# 20_-CONNECT_CONNECTORS.net
KiCad netlist of a schematic drawn in Altium Designer
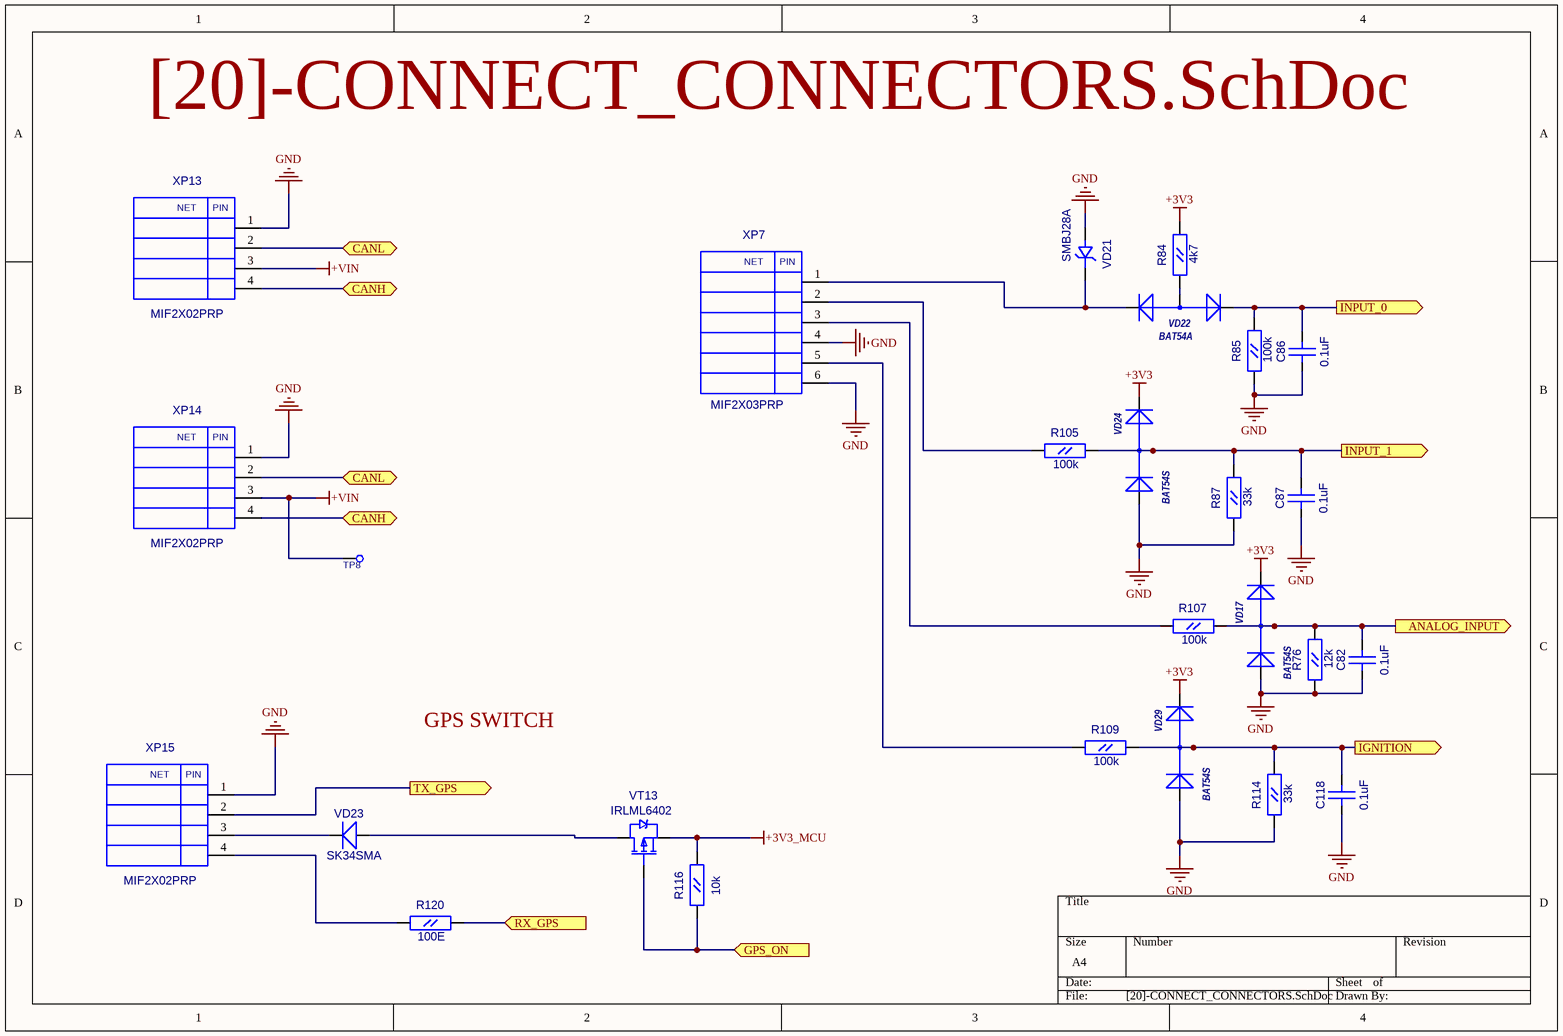
[diagram p0: [20]-CONNECT_CONNECTORS.SchDoc]

(export (version "E")
  (design (tool "Eeschema 10.0.6"))
  (components
    (comp (ref "C82")
      (value "0.1uF")
      (footprint "CC0603")
      (description "CC0603")
      (libsource (lib "gprs_modem_2") (part "CC0603"))
    )
    (comp (ref "C86")
      (value "0.1uF")
      (footprint "CC0603")
      (description "CC0603")
      (libsource (lib "fizik_lib") (part "CC0603"))
    )
    (comp (ref "C87")
      (value "0.1uF")
      (footprint "CC0603")
      (description "CC0603")
      (libsource (lib "gprs_modem_2") (part "CC0603"))
    )
    (comp (ref "C118")
      (value "0.1uF")
      (footprint "CC0603")
      (description "CC0603")
      (libsource (lib "gprs_modem_2") (part "CC0603"))
    )
    (comp (ref "R76")
      (value "12k")
      (footprint "RC0603")
      (description "RC0603")
      (libsource (lib "gprs_modem_2") (part "RC0603"))
    )
    (comp (ref "R84")
      (value "4k7")
      (footprint "RC0603")
      (description "RC0603")
      (libsource (lib "fizik_lib") (part "RC0603"))
    )
    (comp (ref "R85")
      (value "100k")
      (footprint "RC0603")
      (description "RC0603")
      (libsource (lib "fizik_lib") (part "RC0603"))
    )
    (comp (ref "R87")
      (value "33k")
      (footprint "RC0603")
      (description "RC0603")
      (libsource (lib "fizik_lib") (part "RC0603"))
    )
    (comp (ref "R105")
      (value "100k")
      (footprint "RC0603")
      (description "RC0603")
      (libsource (lib "gprs_modem_2") (part "RC0603"))
    )
    (comp (ref "R107")
      (value "100k")
      (footprint "RC0603")
      (description "RC0603")
      (libsource (lib "gprs_modem_2") (part "RC0603"))
    )
    (comp (ref "R109")
      (value "100k")
      (footprint "RC0603")
      (description "RC0603")
      (libsource (lib "gprs_modem_2") (part "RC0603"))
    )
    (comp (ref "R114")
      (value "33k")
      (footprint "RC0603")
      (description "RC0603")
      (libsource (lib "fizik_lib") (part "RC0603"))
    )
    (comp (ref "R116")
      (value "10k")
      (footprint "RC0603")
      (description "RC0603")
      (libsource (lib "gprs_modem_2") (part "RC0603"))
    )
    (comp (ref "R120")
      (value "100E")
      (footprint "RC0603")
      (description "RC0603")
      (libsource (lib "fizik_lib (1)") (part "RC0603"))
    )
    (comp (ref "TP8")
      (value "TESTPOINT1")
      (footprint "TESTPOINT1")
      (libsource (lib "fizik_lib (1)") (part "TESTPOINT1"))
    )
    (comp (ref "VD17")
      (value "BAT54S")
      (footprint "SOT-23(GSD)")
      (description "1.0 Ampere General Purpose Rectifier")
      (libsource (lib "gprs_modem_2") (part "BAT54S"))
    )
    (comp (ref "VD21")
      (value "SMBJ28A")
      (footprint "SMB")
      (description "SMBJ")
      (libsource (lib "fizik_lib") (part "SMBJ"))
    )
    (comp (ref "VD22")
      (value "BAT54A")
      (footprint "SOT-23(123)")
      (description "1.0 Ampere General Purpose Rectifier")
      (libsource (lib "fizik_lib") (part "BAT54A"))
    )
    (comp (ref "VD23")
      (value "SK34SMA")
      (footprint "SMA")
      (description "Schottky Rectifier")
      (libsource (lib "fizik_lib") (part "SK34SMA"))
    )
    (comp (ref "VD24")
      (value "BAT54S")
      (footprint "SOT-23(GSD)")
      (description "1.0 Ampere General Purpose Rectifier")
      (libsource (lib "fizik_lib") (part "BAT54S"))
    )
    (comp (ref "VD29")
      (value "BAT54S")
      (footprint "SOT-23(GSD)")
      (description "1.0 Ampere General Purpose Rectifier")
      (libsource (lib "fizik_lib") (part "BAT54S"))
    )
    (comp (ref "VT13")
      (value "IRLML6402")
      (footprint "SOT-23(123)")
      (description "HEXFET Power MOSFET")
      (libsource (lib "gprs_modem_2") (part "IRLML6402"))
    )
    (comp (ref "XP7")
      (value "MIF2X03PRP")
      (footprint "MIF2X03PRP")
      (libsource (lib "fizik_lib (1)") (part "MIF2X03PRP"))
    )
    (comp (ref "XP13")
      (value "MIF2X02PRP")
      (footprint "MIF2X02PRP")
      (libsource (lib "fizik_lib") (part "MIF2X02PRP"))
    )
    (comp (ref "XP14")
      (value "MIF2X02PRP")
      (footprint "MIF2X02PRP")
      (libsource (lib "fizik_lib") (part "MIF2X02PRP"))
    )
    (comp (ref "XP15")
      (value "MIF2X02PRP")
      (footprint "MIF2X02PRP")
      (libsource (lib "fizik_lib") (part "MIF2X02PRP"))
    )
  )
  (nets
    (net (code "1") (name "+3V3") (class "Default")
      (node (ref "R84") (pin "2") (pinfunction "B_2") (pintype "passive"))
      (node (ref "VD17") (pin "2") (pinfunction "K_2") (pintype "passive"))
      (node (ref "VD24") (pin "2") (pinfunction "K_2") (pintype "passive"))
      (node (ref "VD29") (pin "2") (pinfunction "K_2") (pintype "passive"))
    )
    (net (code "2") (name "+3V3_MCU") (class "Default")
      (node (ref "R116") (pin "2") (pinfunction "B_2") (pintype "passive"))
      (node (ref "VT13") (pin "2") (pinfunction "S_2") (pintype "passive"))
    )
    (net (code "3") (name "+VIN") (class "Default")
      (node (ref "TP8") (pin "1") (pintype "passive"))
      (node (ref "XP13") (pin "3") (pinfunction "3_3") (pintype "passive"))
      (node (ref "XP14") (pin "3") (pinfunction "3_3") (pintype "passive"))
    )
    (net (code "4") (name "/ANALOG_INPUT") (class "Default")
      (node (ref "C82") (pin "2") (pinfunction "B_2") (pintype "passive"))
      (node (ref "R107") (pin "2") (pinfunction "B_2") (pintype "passive"))
      (node (ref "R76") (pin "2") (pinfunction "B_2") (pintype "passive"))
      (node (ref "VD17") (pin "3") (pinfunction "AK_3") (pintype "passive"))
    )
    (net (code "5") (name "/CANH") (class "Default")
      (node (ref "XP13") (pin "4") (pinfunction "4_4") (pintype "passive"))
      (node (ref "XP14") (pin "4") (pinfunction "4_4") (pintype "passive"))
    )
    (net (code "6") (name "/CANL") (class "Default")
      (node (ref "XP13") (pin "2") (pinfunction "2_2") (pintype "passive"))
      (node (ref "XP14") (pin "2") (pinfunction "2_2") (pintype "passive"))
    )
    (net (code "7") (name "/GPS_ON") (class "Default")
      (node (ref "R116") (pin "1") (pinfunction "A_1") (pintype "passive"))
      (node (ref "VT13") (pin "1") (pinfunction "G_1") (pintype "passive"))
    )
    (net (code "8") (name "/IGNITION") (class "Default")
      (node (ref "C118") (pin "2") (pinfunction "B_2") (pintype "passive"))
      (node (ref "R109") (pin "2") (pinfunction "B_2") (pintype "passive"))
      (node (ref "R114") (pin "2") (pinfunction "B_2") (pintype "passive"))
      (node (ref "VD29") (pin "3") (pinfunction "AK_3") (pintype "passive"))
    )
    (net (code "9") (name "/INPUT_0") (class "Default")
      (node (ref "C86") (pin "2") (pinfunction "B_2") (pintype "passive"))
      (node (ref "R85") (pin "2") (pinfunction "B_2") (pintype "passive"))
      (node (ref "VD22") (pin "2") (pinfunction "K_2") (pintype "passive"))
    )
    (net (code "10") (name "/INPUT_1") (class "Default")
      (node (ref "C87") (pin "2") (pinfunction "B_2") (pintype "passive"))
      (node (ref "R105") (pin "2") (pinfunction "B_2") (pintype "passive"))
      (node (ref "R87") (pin "2") (pinfunction "B_2") (pintype "passive"))
      (node (ref "VD24") (pin "3") (pinfunction "AK_3") (pintype "passive"))
    )
    (net (code "11") (name "/RX_GPS") (class "Default")
      (node (ref "R120") (pin "2") (pinfunction "B_2") (pintype "passive"))
    )
    (net (code "12") (name "/TX_GPS") (class "Default")
      (node (ref "XP15") (pin "2") (pinfunction "2_2") (pintype "passive"))
    )
    (net (code "13") (name "GND") (class "Default")
      (node (ref "C118") (pin "1") (pinfunction "A_1") (pintype "passive"))
      (node (ref "C82") (pin "1") (pinfunction "A_1") (pintype "passive"))
      (node (ref "C86") (pin "1") (pinfunction "A_1") (pintype "passive"))
      (node (ref "C87") (pin "1") (pinfunction "A_1") (pintype "passive"))
      (node (ref "R114") (pin "1") (pinfunction "A_1") (pintype "passive"))
      (node (ref "R76") (pin "1") (pinfunction "A_1") (pintype "passive"))
      (node (ref "R85") (pin "1") (pinfunction "A_1") (pintype "passive"))
      (node (ref "R87") (pin "1") (pinfunction "A_1") (pintype "passive"))
      (node (ref "VD17") (pin "1") (pinfunction "A_1") (pintype "passive"))
      (node (ref "VD21") (pin "1") (pinfunction "A_1") (pintype "passive"))
      (node (ref "VD24") (pin "1") (pinfunction "A_1") (pintype "passive"))
      (node (ref "VD29") (pin "1") (pinfunction "A_1") (pintype "passive"))
      (node (ref "XP13") (pin "1") (pinfunction "1_1") (pintype "passive"))
      (node (ref "XP14") (pin "1") (pinfunction "1_1") (pintype "passive"))
      (node (ref "XP15") (pin "1") (pinfunction "1_1") (pintype "passive"))
      (node (ref "XP7") (pin "4") (pinfunction "4_4") (pintype "passive"))
      (node (ref "XP7") (pin "6") (pinfunction "6_6") (pintype "passive"))
    )
    (net (code "14") (name "Net-(R84-A)") (class "Default")
      (node (ref "R84") (pin "1") (pinfunction "A_1") (pintype "passive"))
      (node (ref "VD22") (pin "3") (pinfunction "A_3") (pintype "passive"))
    )
    (net (code "15") (name "Net-(R105-A)") (class "Default")
      (node (ref "R105") (pin "1") (pinfunction "A_1") (pintype "passive"))
      (node (ref "XP7") (pin "2") (pinfunction "2_2") (pintype "passive"))
    )
    (net (code "16") (name "Net-(R107-A)") (class "Default")
      (node (ref "R107") (pin "1") (pinfunction "A_1") (pintype "passive"))
      (node (ref "XP7") (pin "3") (pinfunction "3_3") (pintype "passive"))
    )
    (net (code "17") (name "Net-(R109-A)") (class "Default")
      (node (ref "R109") (pin "1") (pinfunction "A_1") (pintype "passive"))
      (node (ref "XP7") (pin "5") (pinfunction "5_5") (pintype "passive"))
    )
    (net (code "18") (name "Net-(R120-A)") (class "Default")
      (node (ref "R120") (pin "1") (pinfunction "A_1") (pintype "passive"))
      (node (ref "XP15") (pin "4") (pinfunction "4_4") (pintype "passive"))
    )
    (net (code "19") (name "Net-(VD21-K)") (class "Default")
      (node (ref "VD21") (pin "2") (pinfunction "K_2") (pintype "passive"))
      (node (ref "VD22") (pin "1") (pinfunction "K_1") (pintype "passive"))
      (node (ref "XP7") (pin "1") (pinfunction "1_1") (pintype "passive"))
    )
    (net (code "20") (name "Net-(VD23-A)") (class "Default")
      (node (ref "VD23") (pin "1") (pinfunction "A_1") (pintype "passive"))
      (node (ref "VT13") (pin "3") (pinfunction "D_3") (pintype "passive"))
    )
    (net (code "21") (name "Net-(VD23-K)") (class "Default")
      (node (ref "VD23") (pin "2") (pinfunction "K_2") (pintype "passive"))
      (node (ref "XP15") (pin "3") (pinfunction "3_3") (pintype "passive"))
    )
  )
)
